# Evacuation_robot_arduino_shield.net
KiCad netlist of a schematic drawn in EAGLE
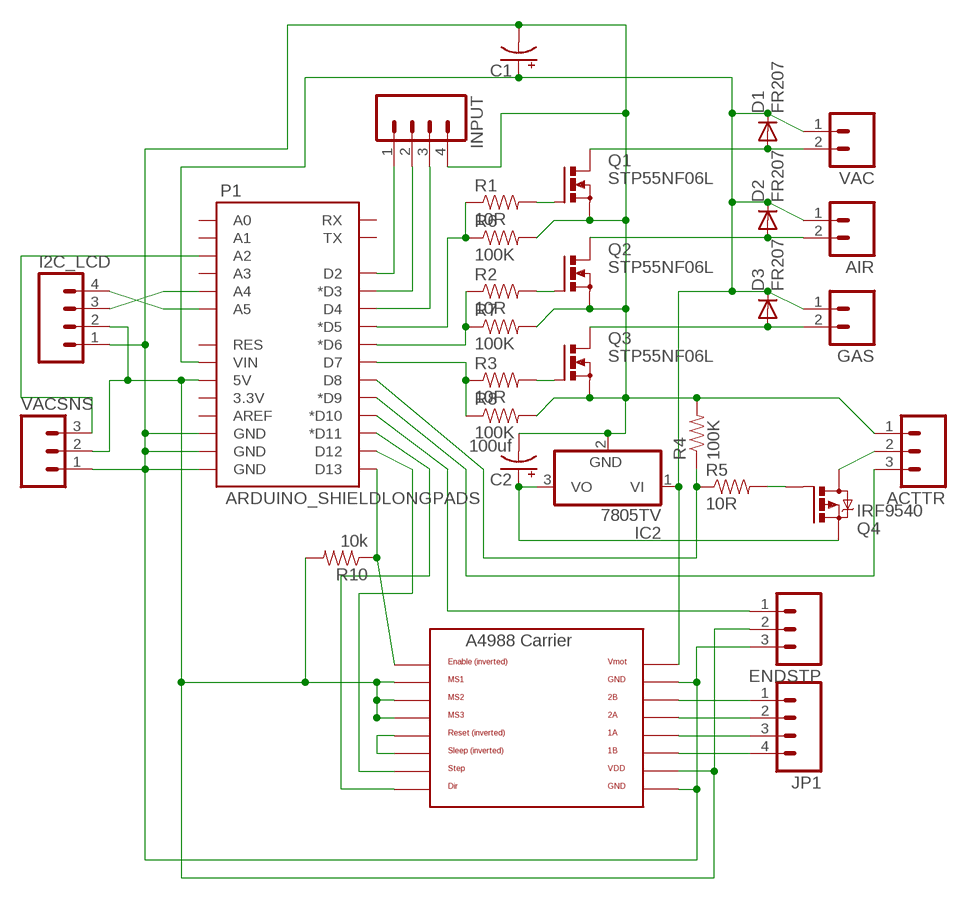
[diagram p0: schematic, sheet 1]

(export (version "E")
  (design (tool "Eeschema 10.0.6"))
  (components
    (comp (ref "ACTTR")
      (value "M03LONGPADS")
      (footprint "eagle-import:1X03_LONGPADS")
      (libsource (lib "eagle-import") (part "M03LONGPADS"))
    )
    (comp (ref "AIR")
      (value "M02PTH3")
      (footprint "eagle-import:1X02_LONGPADS")
      (libsource (lib "eagle-import") (part "M02PTH3"))
    )
    (comp (ref "C1")
      (value "CAP_POLPTH4")
      (footprint "eagle-import:CPOL-RADIAL-1000UF-25V")
      (libsource (lib "eagle-import") (part "CAP_POLPTH4"))
    )
    (comp (ref "C2")
      (value "100uf")
      (footprint "eagle-import:CPOL-RADIAL-100UF-25V")
      (libsource (lib "eagle-import") (part "CAP_POLPTH1"))
    )
    (comp (ref "D1")
      (value "FR207")
      (footprint "eagle-import:DIODE-1N4148")
      (libsource (lib "eagle-import") (part "DIODE1N4148"))
    )
    (comp (ref "D2")
      (value "FR207")
      (footprint "eagle-import:DIODE-1N4148")
      (libsource (lib "eagle-import") (part "DIODE1N4148"))
    )
    (comp (ref "D3")
      (value "FR207")
      (footprint "eagle-import:DIODE-1N4148")
      (libsource (lib "eagle-import") (part "DIODE1N4148"))
    )
    (comp (ref "ENDSTP")
      (value "M03LONGPADS")
      (footprint "eagle-import:1X03_LONGPADS")
      (libsource (lib "eagle-import") (part "M03LONGPADS"))
    )
    (comp (ref "GAS")
      (value "M02PTH3")
      (footprint "eagle-import:1X02_LONGPADS")
      (libsource (lib "eagle-import") (part "M02PTH3"))
    )
    (comp (ref "I2C_LCD")
      (value "M04LONGPADS")
      (footprint "eagle-import:1X04_LONGPADS")
      (libsource (lib "eagle-import") (part "M04LONGPADS"))
    )
    (comp (ref "IC2")
      (value "7805TV")
      (footprint "eagle-import:TO220V")
      (libsource (lib "eagle-import") (part "78TV05"))
    )
    (comp (ref "INPUT")
      (value "M04LONGPADS")
      (footprint "eagle-import:1X04_LONGPADS")
      (libsource (lib "eagle-import") (part "M04LONGPADS"))
    )
    (comp (ref "JP1")
      (value "M04LONGPADS")
      (footprint "eagle-import:1X04_LONGPADS")
      (libsource (lib "eagle-import") (part "M04LONGPADS"))
    )
    (comp (ref "P1")
      (value "ARDUINO_SHIELDLONGPADS")
      (footprint "eagle-import:DUEMILANOVE_SHIELD_LONGPADS")
      (libsource (lib "eagle-import") (part "ARDUINO_SHIELDLONGPADS"))
    )
    (comp (ref "Q1")
      (value "STP55NF06L")
      (footprint "eagle-import:TO220BV")
      (libsource (lib "eagle-import") (part "PMOSFET_NTO220BV"))
    )
    (comp (ref "Q2")
      (value "STP55NF06L")
      (footprint "eagle-import:TO220BV")
      (libsource (lib "eagle-import") (part "PMOSFET_NTO220BV"))
    )
    (comp (ref "Q3")
      (value "STP55NF06L")
      (footprint "eagle-import:TO220BV")
      (libsource (lib "eagle-import") (part "PMOSFET_NTO220BV"))
    )
    (comp (ref "Q4")
      (value "IRF9540")
      (footprint "eagle-import:TO220BV")
      (libsource (lib "eagle-import") (part "IRF9530"))
    )
    (comp (ref "R1")
      (value "10R")
      (footprint "eagle-import:AXIAL-0.3")
      (libsource (lib "eagle-import") (part "RESISTORAXIAL-0.3"))
    )
    (comp (ref "R2")
      (value "10R")
      (footprint "eagle-import:AXIAL-0.3")
      (libsource (lib "eagle-import") (part "RESISTORAXIAL-0.3"))
    )
    (comp (ref "R3")
      (value "10R")
      (footprint "eagle-import:AXIAL-0.3")
      (libsource (lib "eagle-import") (part "RESISTORAXIAL-0.3"))
    )
    (comp (ref "R4")
      (value "100K")
      (footprint "eagle-import:AXIAL-0.3")
      (libsource (lib "eagle-import") (part "RESISTORAXIAL-0.3"))
    )
    (comp (ref "R5")
      (value "10R")
      (footprint "eagle-import:AXIAL-0.3")
      (libsource (lib "eagle-import") (part "RESISTORAXIAL-0.3"))
    )
    (comp (ref "R6")
      (value "100K")
      (footprint "eagle-import:AXIAL-0.3")
      (libsource (lib "eagle-import") (part "RESISTORAXIAL-0.3"))
    )
    (comp (ref "R7")
      (value "100K")
      (footprint "eagle-import:AXIAL-0.3")
      (libsource (lib "eagle-import") (part "RESISTORAXIAL-0.3"))
    )
    (comp (ref "R8")
      (value "100K")
      (footprint "eagle-import:AXIAL-0.3")
      (libsource (lib "eagle-import") (part "RESISTORAXIAL-0.3"))
    )
    (comp (ref "R10")
      (value "10k")
      (footprint "eagle-import:AXIAL-0.3")
      (libsource (lib "eagle-import") (part "RESISTORAXIAL-0.3"))
    )
    (comp (ref "U$1")
      (value "A4988BREAKOUT")
      (footprint "eagle-import:A4988BREAKOUT")
      (libsource (lib "eagle-import") (part "A4988BREAKOUT"))
    )
    (comp (ref "VAC")
      (value "M02PTH3")
      (footprint "eagle-import:1X02_LONGPADS")
      (libsource (lib "eagle-import") (part "M02PTH3"))
    )
    (comp (ref "VACSNS")
      (value "M03LONGPADS")
      (footprint "eagle-import:1X03_LONGPADS")
      (libsource (lib "eagle-import") (part "M03LONGPADS"))
    )
  )
  (nets
    (net (code "1") (name "Net-(ACTTR-Pad2)") (class "Default")
      (node (ref "ACTTR") (pin "2") (pinfunction "2_2") (pintype "passive"))
      (node (ref "Q4") (pin "D") (pinfunction "D_D") (pintype "passive"))
    )
    (net (code "2") (name "Net-(AIR-Pad2)") (class "Default")
      (node (ref "AIR") (pin "2") (pinfunction "2_2") (pintype "passive"))
      (node (ref "D2") (pin "A") (pinfunction "A_A") (pintype "passive"))
      (node (ref "Q2") (pin "D") (pinfunction "D_D") (pintype "passive"))
    )
    (net (code "3") (name "Net-(C1-+)") (class "Default")
      (node (ref "AIR") (pin "1") (pinfunction "1_1") (pintype "passive"))
      (node (ref "C1") (pin "1") (pinfunction "+_1") (pintype "passive"))
      (node (ref "D1") (pin "C") (pinfunction "C_C") (pintype "passive"))
      (node (ref "D2") (pin "C") (pinfunction "C_C") (pintype "passive"))
      (node (ref "D3") (pin "C") (pinfunction "C_C") (pintype "passive"))
      (node (ref "GAS") (pin "1") (pinfunction "1_1") (pintype "passive"))
      (node (ref "IC2") (pin "1") (pinfunction "VI_1") (pintype "input"))
      (node (ref "P1") (pin "VIN") (pinfunction "VIN_VIN") (pintype "bidirectional"))
      (node (ref "U$1") (pin "VMOT") (pinfunction "VMOT_VMOT") (pintype "power_in"))
      (node (ref "VAC") (pin "1") (pinfunction "1_1") (pintype "passive"))
    )
    (net (code "4") (name "Net-(C1--)") (class "Default")
      (node (ref "ACTTR") (pin "1") (pinfunction "1_1") (pintype "passive"))
      (node (ref "C1") (pin "2") (pinfunction "-_2") (pintype "passive"))
      (node (ref "C2") (pin "2") (pinfunction "-_2") (pintype "passive"))
      (node (ref "ENDSTP") (pin "3") (pinfunction "3_3") (pintype "passive"))
      (node (ref "I2C_LCD") (pin "1") (pinfunction "1_1") (pintype "passive"))
      (node (ref "IC2") (pin "2") (pinfunction "GND_2") (pintype "passive"))
      (node (ref "INPUT") (pin "4") (pinfunction "4_4") (pintype "passive"))
      (node (ref "P1") (pin "GND@0") (pinfunction "GND_GND@0") (pintype "bidirectional"))
      (node (ref "P1") (pin "GND@1") (pinfunction "GND_GND@1") (pintype "bidirectional"))
      (node (ref "P1") (pin "GND@2") (pinfunction "GND_GND@2") (pintype "bidirectional"))
      (node (ref "Q1") (pin "S") (pinfunction "S_S") (pintype "passive"))
      (node (ref "Q2") (pin "S") (pinfunction "S_S") (pintype "passive"))
      (node (ref "Q3") (pin "S") (pinfunction "S_S") (pintype "passive"))
      (node (ref "R4") (pin "P$2") (pinfunction "2_P$2") (pintype "passive"))
      (node (ref "R6") (pin "P$2") (pinfunction "2_P$2") (pintype "passive"))
      (node (ref "R7") (pin "P$2") (pinfunction "2_P$2") (pintype "passive"))
      (node (ref "R8") (pin "P$2") (pinfunction "2_P$2") (pintype "passive"))
      (node (ref "U$1") (pin "GND") (pinfunction "GND_GND") (pintype "power_in"))
      (node (ref "U$1") (pin "GND@0") (pinfunction "GND_GND@0") (pintype "power_in"))
      (node (ref "VACSNS") (pin "1") (pinfunction "1_1") (pintype "passive"))
    )
    (net (code "5") (name "Net-(C2-+)") (class "Default")
      (node (ref "C2") (pin "1") (pinfunction "+_1") (pintype "passive"))
      (node (ref "IC2") (pin "3") (pinfunction "VO_3") (pintype "passive"))
      (node (ref "Q4") (pin "S") (pinfunction "S_S") (pintype "passive"))
    )
    (net (code "6") (name "Net-(D1-PadA)") (class "Default")
      (node (ref "D1") (pin "A") (pinfunction "A_A") (pintype "passive"))
      (node (ref "Q1") (pin "D") (pinfunction "D_D") (pintype "passive"))
      (node (ref "VAC") (pin "2") (pinfunction "2_2") (pintype "passive"))
    )
    (net (code "7") (name "Net-(D3-PadA)") (class "Default")
      (node (ref "D3") (pin "A") (pinfunction "A_A") (pintype "passive"))
      (node (ref "GAS") (pin "2") (pinfunction "2_2") (pintype "passive"))
      (node (ref "Q3") (pin "D") (pinfunction "D_D") (pintype "passive"))
    )
    (net (code "8") (name "Net-(I2C_LCD-Pad3)") (class "Default")
      (node (ref "I2C_LCD") (pin "3") (pinfunction "3_3") (pintype "passive"))
      (node (ref "P1") (pin "A4") (pinfunction "A4_A4") (pintype "bidirectional"))
    )
    (net (code "9") (name "Net-(I2C_LCD-Pad4)") (class "Default")
      (node (ref "I2C_LCD") (pin "4") (pinfunction "4_4") (pintype "passive"))
      (node (ref "P1") (pin "A5") (pinfunction "A5_A5") (pintype "bidirectional"))
    )
    (net (code "10") (name "Net-(INPUT-Pad1)") (class "Default")
      (node (ref "INPUT") (pin "1") (pinfunction "1_1") (pintype "passive"))
      (node (ref "P1") (pin "D2") (pinfunction "D2_D2") (pintype "bidirectional"))
    )
    (net (code "11") (name "Net-(INPUT-Pad3)") (class "Default")
      (node (ref "INPUT") (pin "3") (pinfunction "3_3") (pintype "passive"))
      (node (ref "P1") (pin "D4") (pinfunction "D4_D4") (pintype "bidirectional"))
    )
    (net (code "12") (name "Net-(JP1-Pad1)") (class "Default")
      (node (ref "JP1") (pin "1") (pinfunction "1_1") (pintype "passive"))
      (node (ref "U$1") (pin "2B") (pinfunction "2B_2B") (pintype "output"))
    )
    (net (code "13") (name "Net-(JP1-Pad2)") (class "Default")
      (node (ref "JP1") (pin "2") (pinfunction "2_2") (pintype "passive"))
      (node (ref "U$1") (pin "2A") (pinfunction "2A_2A") (pintype "output"))
    )
    (net (code "14") (name "Net-(JP1-Pad3)") (class "Default")
      (node (ref "JP1") (pin "3") (pinfunction "3_3") (pintype "passive"))
      (node (ref "U$1") (pin "1A") (pinfunction "1A_1A") (pintype "output"))
    )
    (net (code "15") (name "Net-(JP1-Pad4)") (class "Default")
      (node (ref "JP1") (pin "4") (pinfunction "4_4") (pintype "passive"))
      (node (ref "U$1") (pin "1B") (pinfunction "1B_1B") (pintype "output"))
    )
    (net (code "16") (name "Net-(P1-*D3)") (class "Default")
      (node (ref "INPUT") (pin "2") (pinfunction "2_2") (pintype "passive"))
      (node (ref "P1") (pin "D3") (pinfunction "*D3_D3") (pintype "bidirectional"))
    )
    (net (code "17") (name "Net-(P1-*D5)") (class "Default")
      (node (ref "P1") (pin "D5") (pinfunction "*D5_D5") (pintype "bidirectional"))
      (node (ref "R1") (pin "P$1") (pinfunction "1_P$1") (pintype "passive"))
      (node (ref "R6") (pin "P$1") (pinfunction "1_P$1") (pintype "passive"))
    )
    (net (code "18") (name "Net-(P1-*D6)") (class "Default")
      (node (ref "P1") (pin "D6") (pinfunction "*D6_D6") (pintype "bidirectional"))
      (node (ref "R2") (pin "P$1") (pinfunction "1_P$1") (pintype "passive"))
      (node (ref "R7") (pin "P$1") (pinfunction "1_P$1") (pintype "passive"))
    )
    (net (code "19") (name "Net-(P1-*D9)") (class "Default")
      (node (ref "ACTTR") (pin "3") (pinfunction "3_3") (pintype "passive"))
      (node (ref "P1") (pin "D9") (pinfunction "*D9_D9") (pintype "bidirectional"))
    )
    (net (code "20") (name "Net-(P1-*D10)") (class "Default")
      (node (ref "ENDSTP") (pin "1") (pinfunction "1_1") (pintype "passive"))
      (node (ref "P1") (pin "D10") (pinfunction "*D10_D10") (pintype "bidirectional"))
    )
    (net (code "21") (name "Net-(P1-*D11)") (class "Default")
      (node (ref "P1") (pin "D11") (pinfunction "*D11_D11") (pintype "bidirectional"))
      (node (ref "U$1") (pin "DIR") (pinfunction "DIR_DIR") (pintype "input"))
    )
    (net (code "22") (name "Net-(P1-PadA2)") (class "Default")
      (node (ref "P1") (pin "A2") (pinfunction "A2_A2") (pintype "bidirectional"))
      (node (ref "VACSNS") (pin "3") (pinfunction "3_3") (pintype "passive"))
    )
    (net (code "23") (name "Net-(P1-PadD12)") (class "Default")
      (node (ref "P1") (pin "D12") (pinfunction "D12_D12") (pintype "bidirectional"))
      (node (ref "U$1") (pin "STEP") (pinfunction "STEP_STEP") (pintype "input"))
    )
    (net (code "24") (name "Net-(R1-2)") (class "Default")
      (node (ref "Q1") (pin "G") (pinfunction "G_G") (pintype "passive"))
      (node (ref "R1") (pin "P$2") (pinfunction "2_P$2") (pintype "passive"))
    )
    (net (code "25") (name "Net-(R2-2)") (class "Default")
      (node (ref "Q2") (pin "G") (pinfunction "G_G") (pintype "passive"))
      (node (ref "R2") (pin "P$2") (pinfunction "2_P$2") (pintype "passive"))
    )
    (net (code "26") (name "Net-(R3-1)") (class "Default")
      (node (ref "P1") (pin "D7") (pinfunction "D7_D7") (pintype "bidirectional"))
      (node (ref "R3") (pin "P$1") (pinfunction "1_P$1") (pintype "passive"))
      (node (ref "R8") (pin "P$1") (pinfunction "1_P$1") (pintype "passive"))
    )
    (net (code "27") (name "Net-(R3-2)") (class "Default")
      (node (ref "Q3") (pin "G") (pinfunction "G_G") (pintype "passive"))
      (node (ref "R3") (pin "P$2") (pinfunction "2_P$2") (pintype "passive"))
    )
    (net (code "28") (name "Net-(R4-1)") (class "Default")
      (node (ref "P1") (pin "D8") (pinfunction "D8_D8") (pintype "bidirectional"))
      (node (ref "R4") (pin "P$1") (pinfunction "1_P$1") (pintype "passive"))
      (node (ref "R5") (pin "P$1") (pinfunction "1_P$1") (pintype "passive"))
    )
    (net (code "29") (name "Net-(R5-2)") (class "Default")
      (node (ref "Q4") (pin "G") (pinfunction "G_G") (pintype "passive"))
      (node (ref "R5") (pin "P$2") (pinfunction "2_P$2") (pintype "passive"))
    )
    (net (code "30") (name "Net-(R10-1)") (class "Default")
      (node (ref "P1") (pin "D13") (pinfunction "D13_D13") (pintype "bidirectional"))
      (node (ref "R10") (pin "P$1") (pinfunction "1_P$1") (pintype "passive"))
      (node (ref "U$1") (pin "EN") (pinfunction "EN_EN") (pintype "input"))
    )
    (net (code "31") (name "Net-(R10-2)") (class "Default")
      (node (ref "ENDSTP") (pin "2") (pinfunction "2_2") (pintype "passive"))
      (node (ref "I2C_LCD") (pin "2") (pinfunction "2_2") (pintype "passive"))
      (node (ref "P1") (pin "5V") (pinfunction "5V_5V") (pintype "bidirectional"))
      (node (ref "R10") (pin "P$2") (pinfunction "2_P$2") (pintype "passive"))
      (node (ref "U$1") (pin "MS1") (pinfunction "MS1_MS1") (pintype "input"))
      (node (ref "U$1") (pin "MS2") (pinfunction "MS2_MS2") (pintype "input"))
      (node (ref "U$1") (pin "MS3") (pinfunction "MS3_MS3") (pintype "input"))
      (node (ref "U$1") (pin "VDD") (pinfunction "VDD_VDD") (pintype "power_in"))
      (node (ref "VACSNS") (pin "2") (pinfunction "2_2") (pintype "passive"))
    )
    (net (code "32") (name "Net-(U$1-SLEEP)") (class "Default")
      (node (ref "U$1") (pin "RST") (pinfunction "RST_RST") (pintype "input"))
      (node (ref "U$1") (pin "SLP") (pinfunction "SLEEP_SLP") (pintype "input"))
    )
    (net (code "33") (name "unconnected-(P1-Pad3.3V)") (class "Default")
      (node (ref "P1") (pin "3.3V") (pinfunction "3.3V_3.3V") (pintype "bidirectional"))
    )
    (net (code "34") (name "unconnected-(P1-PadA0)") (class "Default")
      (node (ref "P1") (pin "A0") (pinfunction "A0_A0") (pintype "bidirectional"))
    )
    (net (code "35") (name "unconnected-(P1-PadA1)") (class "Default")
      (node (ref "P1") (pin "A1") (pinfunction "A1_A1") (pintype "bidirectional"))
    )
    (net (code "36") (name "unconnected-(P1-PadA3)") (class "Default")
      (node (ref "P1") (pin "A3") (pinfunction "A3_A3") (pintype "bidirectional"))
    )
    (net (code "37") (name "unconnected-(P1-PadAREF)") (class "Default")
      (node (ref "P1") (pin "AREF") (pinfunction "AREF_AREF") (pintype "bidirectional"))
    )
    (net (code "38") (name "unconnected-(P1-PadRES)") (class "Default")
      (node (ref "P1") (pin "RES") (pinfunction "RES_RES") (pintype "bidirectional"))
    )
    (net (code "39") (name "unconnected-(P1-PadRX)") (class "Default")
      (node (ref "P1") (pin "RX") (pinfunction "RX_RX") (pintype "bidirectional"))
    )
    (net (code "40") (name "unconnected-(P1-PadTX)") (class "Default")
      (node (ref "P1") (pin "TX") (pinfunction "TX_TX") (pintype "bidirectional"))
    )
  )
)
